# switch_pcb.net
KiCad netlist of a schematic drawn in EAGLE
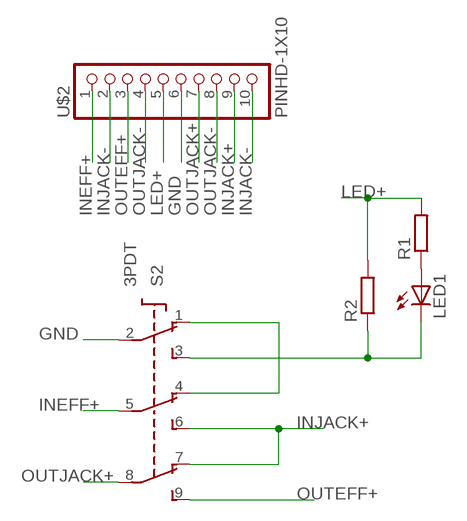
[diagram p0: schematic, sheet 1]

(export (version "E")
  (design (tool "Eeschema 10.0.6"))
  (components
    (comp (ref "LED1")
      (value "LED3MM")
      (footprint "eagle-import:LED3MM")
      (libsource (lib "eagle-import") (part "LED3MM"))
    )
    (comp (ref "R1")
      (value "R-EU_R0603")
      (footprint "eagle-import:R0603")
      (libsource (lib "eagle-import") (part "R-EU_R0603"))
    )
    (comp (ref "R2")
      (value "R-EU_R0603")
      (footprint "eagle-import:R0603")
      (libsource (lib "eagle-import") (part "R-EU_R0603"))
    )
    (comp (ref "S2")
      (value "3PDT")
      (footprint "eagle-import:3PDT")
      (libsource (lib "eagle-import") (part "3PDT"))
    )
    (comp (ref "U$2")
      (value "PINHD-1X10")
      (footprint "eagle-import:1X10-BIG")
      (libsource (lib "eagle-import") (part "PINHD-1X10"))
    )
  )
  (nets
    (net (code "1") (name "/GND") (class "Default")
      (node (ref "S2") (pin "2") (pinfunction "P1_2") (pintype "passive"))
      (node (ref "U$2") (pin "6") (pinfunction "6_6") (pintype "passive"))
    )
    (net (code "2") (name "/INEFF+") (class "Default")
      (node (ref "S2") (pin "5") (pinfunction "P2_5") (pintype "passive"))
      (node (ref "U$2") (pin "1") (pinfunction "1_1") (pintype "passive"))
    )
    (net (code "3") (name "/INJACK+") (class "Default")
      (node (ref "S2") (pin "6") (pinfunction "S2_6") (pintype "passive"))
      (node (ref "S2") (pin "7") (pinfunction "O3_7") (pintype "passive"))
      (node (ref "U$2") (pin "9") (pinfunction "9_9") (pintype "passive"))
    )
    (net (code "4") (name "/INJACK-") (class "Default")
      (node (ref "U$2") (pin "10") (pinfunction "10_10") (pintype "passive"))
      (node (ref "U$2") (pin "2") (pinfunction "2_2") (pintype "passive"))
    )
    (net (code "5") (name "/LED+") (class "Default")
      (node (ref "R1") (pin "2") (pinfunction "2_2") (pintype "passive"))
      (node (ref "R2") (pin "2") (pinfunction "2_2") (pintype "passive"))
      (node (ref "U$2") (pin "5") (pinfunction "5_5") (pintype "passive"))
    )
    (net (code "6") (name "/OUTEFF+") (class "Default")
      (node (ref "S2") (pin "9") (pinfunction "S3_9") (pintype "passive"))
      (node (ref "U$2") (pin "3") (pinfunction "3_3") (pintype "passive"))
    )
    (net (code "7") (name "/OUTJACK+") (class "Default")
      (node (ref "S2") (pin "8") (pinfunction "P3_8") (pintype "passive"))
      (node (ref "U$2") (pin "7") (pinfunction "7_7") (pintype "passive"))
    )
    (net (code "8") (name "/OUTJACK-") (class "Default")
      (node (ref "U$2") (pin "4") (pinfunction "4_4") (pintype "passive"))
      (node (ref "U$2") (pin "8") (pinfunction "8_8") (pintype "passive"))
    )
    (net (code "9") (name "Net-(LED1-C)") (class "Default")
      (node (ref "LED1") (pin "K") (pinfunction "C_K") (pintype "passive"))
      (node (ref "R2") (pin "1") (pinfunction "1_1") (pintype "passive"))
      (node (ref "S2") (pin "3") (pinfunction "S1_3") (pintype "passive"))
    )
    (net (code "10") (name "Net-(LED1-PadA)") (class "Default")
      (node (ref "LED1") (pin "A") (pinfunction "A_A") (pintype "passive"))
      (node (ref "R1") (pin "1") (pinfunction "1_1") (pintype "passive"))
    )
    (net (code "11") (name "Net-(S2-O1)") (class "Default")
      (node (ref "S2") (pin "1") (pinfunction "O1_1") (pintype "passive"))
      (node (ref "S2") (pin "4") (pinfunction "O2_4") (pintype "passive"))
    )
  )
)
